# yellowstone-walach-aerospace-cubesat-sch.net
KiCad netlist of a schematic drawn in EAGLE
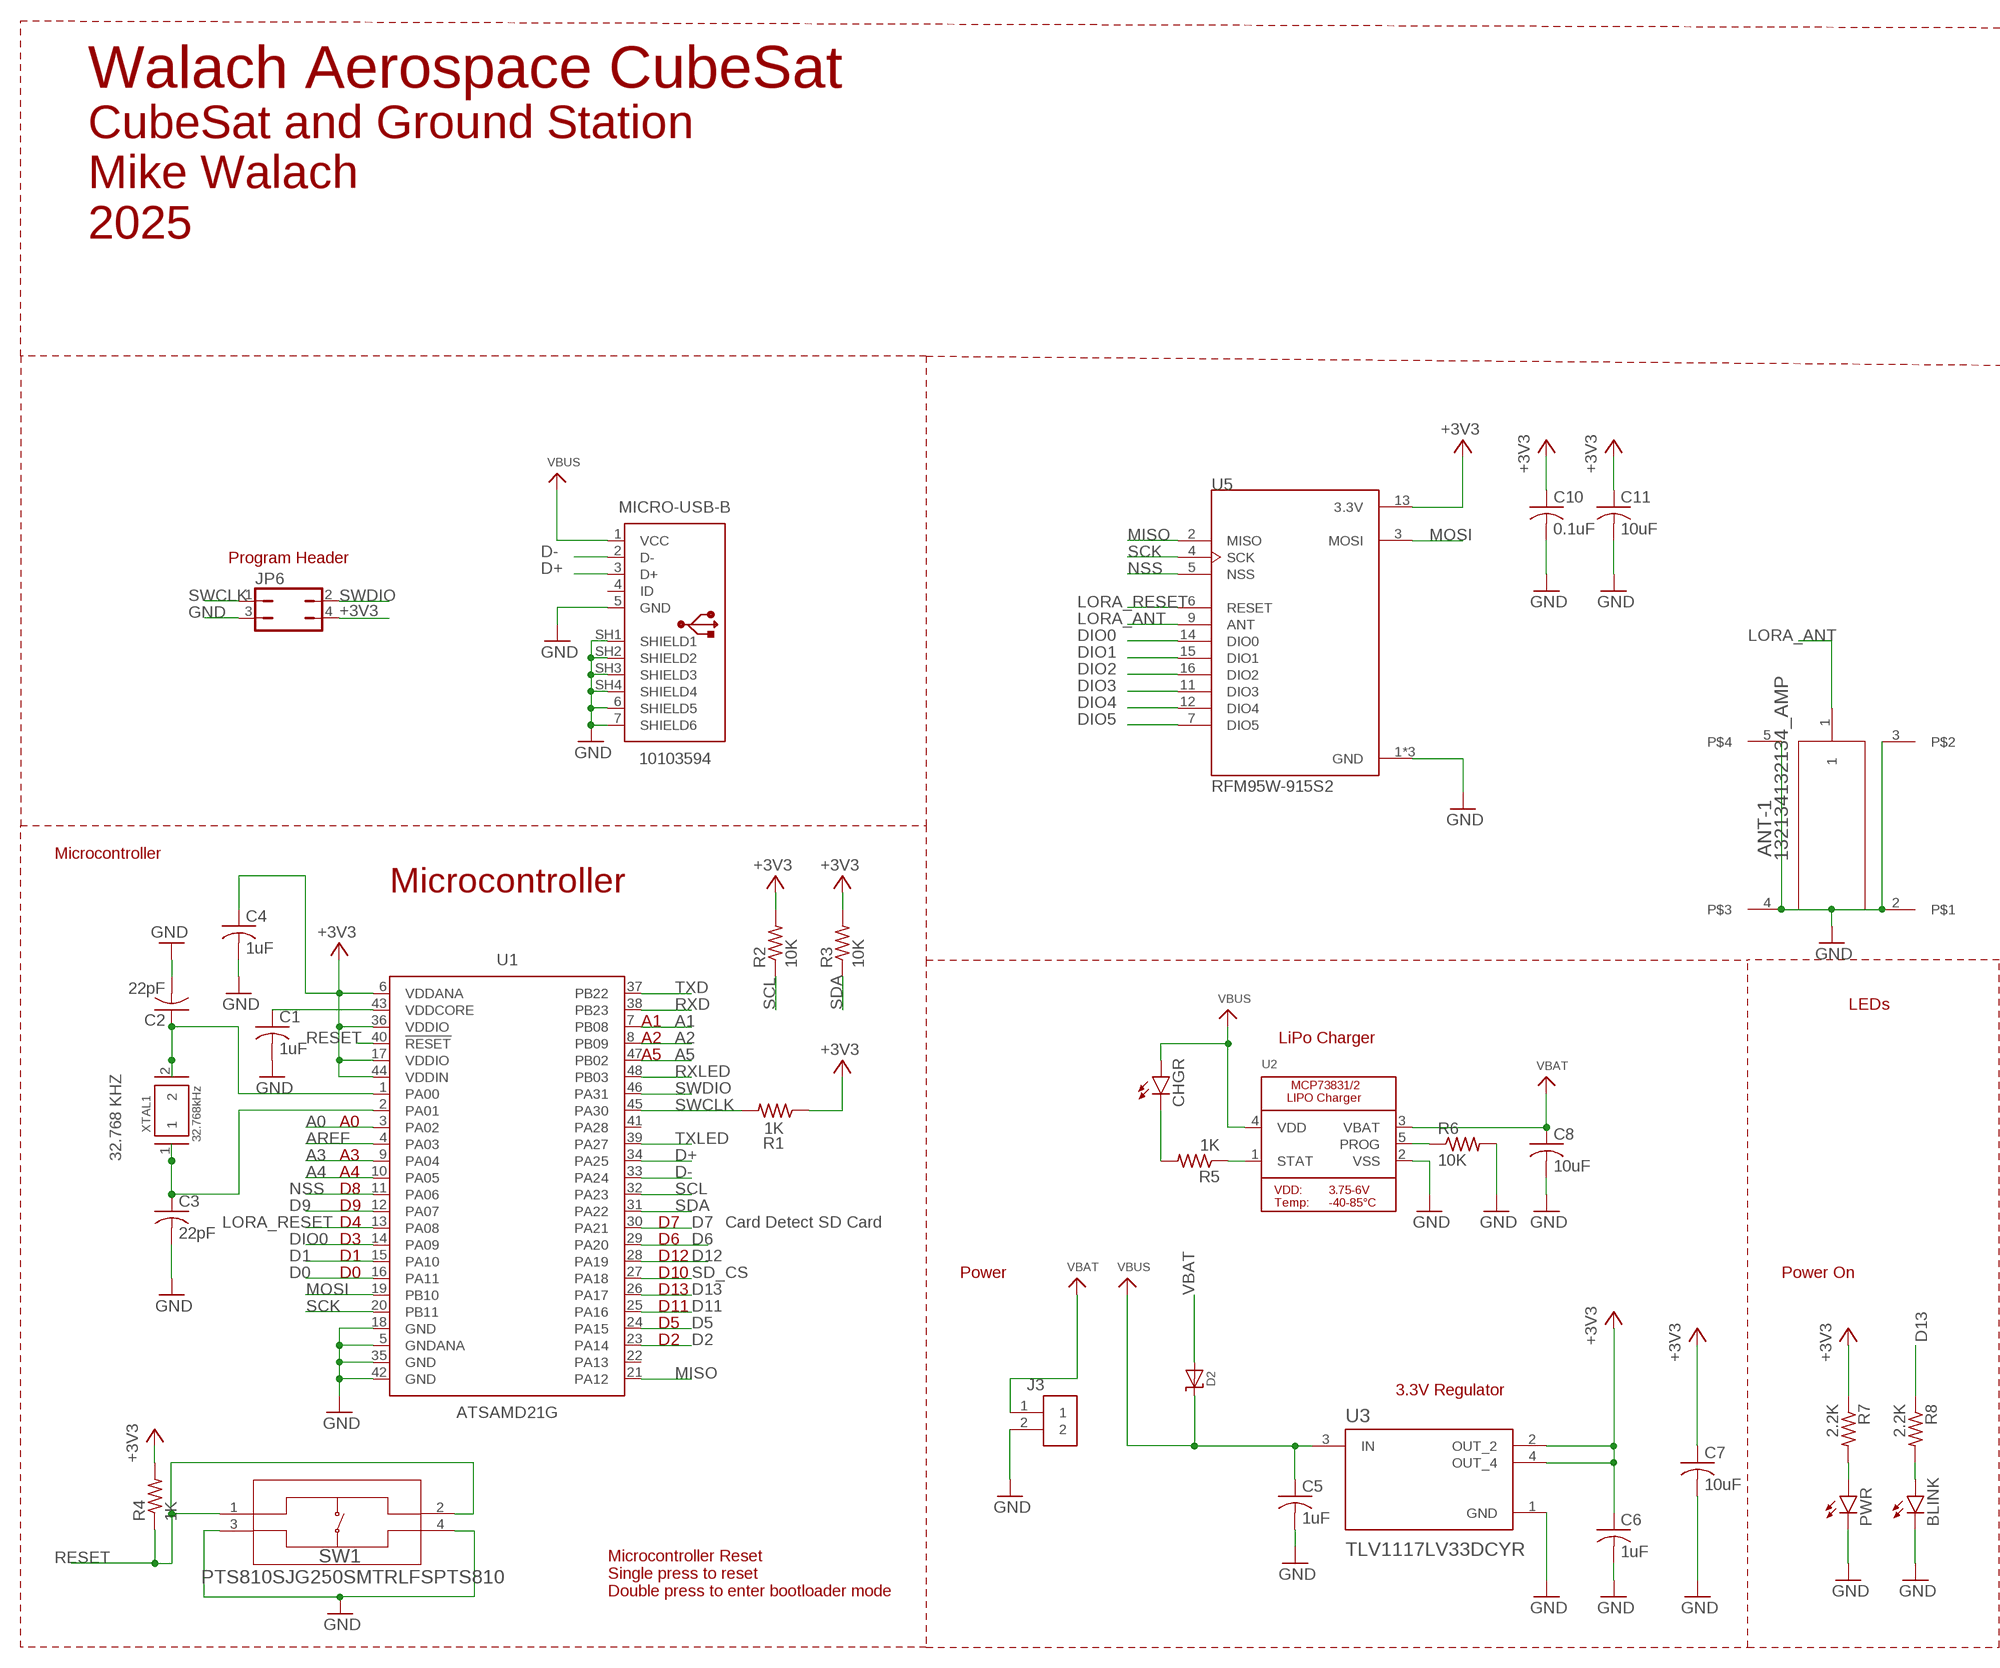
[diagram p0: schematic, sheet 1, part 1 of 2]
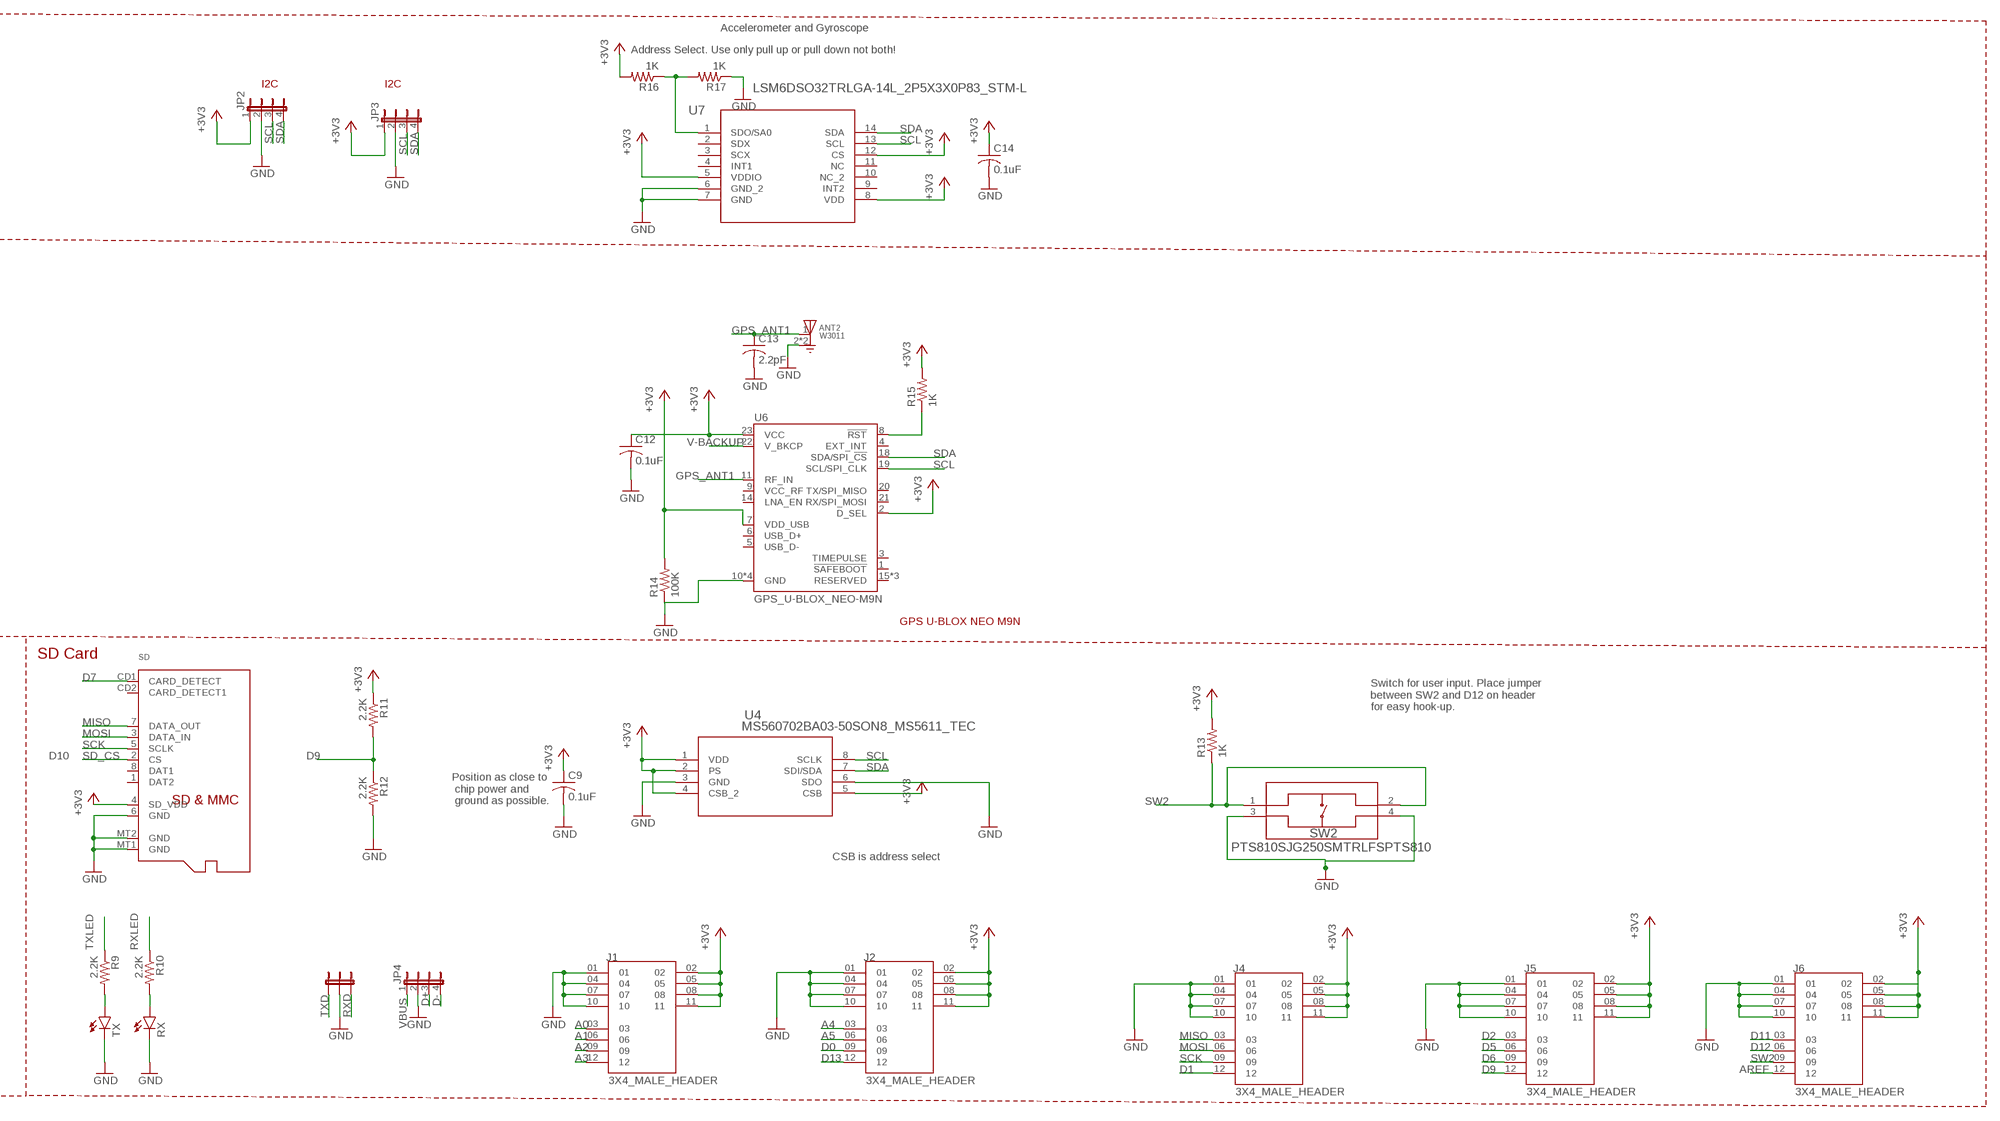
[diagram p1: schematic, sheet 1, part 2 of 2]

(export (version "E")
  (design (tool "Eeschema 10.0.6"))
  (components
    (comp (ref "ANT-1")
      (value "132134132134_AMP")
      (footprint "eagle-import:132134_AMP")
      (fields
        (field (name "MANUFACTURER_PART_NUMBER") "132134")
        (field (name "COPYRIGHT") "Copyright (C) 2025 Ultra Librarian. All rights reserved.")
      )
      (libsource (lib "eagle-import") (part "132134132134_AMP"))
    )
    (comp (ref "ANT2")
      (value "W3011")
      (footprint "eagle-import:XDCR_W3011")
      (fields (field (name "MANUFACTURER") "PulseLarsen"))
      (libsource (lib "eagle-import") (part "W3011"))
    )
    (comp (ref "BLINK")
      (value "LEDSML0805")
      (footprint "eagle-import:SML0805")
      (libsource (lib "eagle-import") (part "LEDSML0805"))
    )
    (comp (ref "C1")
      (value "1uF")
      (footprint "eagle-import:C0805")
      (libsource (lib "eagle-import") (part "C-USC0805"))
    )
    (comp (ref "C2")
      (value "22pF")
      (footprint "eagle-import:C0805")
      (libsource (lib "eagle-import") (part "C-USC0805"))
    )
    (comp (ref "C3")
      (value "22pF")
      (footprint "eagle-import:C0805")
      (libsource (lib "eagle-import") (part "C-USC0805"))
    )
    (comp (ref "C4")
      (value "1uF")
      (footprint "eagle-import:C0805")
      (libsource (lib "eagle-import") (part "C-USC0805"))
    )
    (comp (ref "C5")
      (value "1uF")
      (footprint "eagle-import:C0805")
      (libsource (lib "eagle-import") (part "C-USC0805"))
    )
    (comp (ref "C6")
      (value "1uF")
      (footprint "eagle-import:C0805")
      (libsource (lib "eagle-import") (part "C-USC0805"))
    )
    (comp (ref "C7")
      (value "10uF")
      (footprint "eagle-import:C0805")
      (libsource (lib "eagle-import") (part "C-USC0805"))
    )
    (comp (ref "C8")
      (value "10uF")
      (footprint "eagle-import:C0805")
      (libsource (lib "eagle-import") (part "C-USC0805"))
    )
    (comp (ref "C9")
      (value "0.1uF")
      (footprint "eagle-import:C0805")
      (libsource (lib "eagle-import") (part "C-USC0805"))
    )
    (comp (ref "C10")
      (value "0.1uF")
      (footprint "eagle-import:C0805")
      (libsource (lib "eagle-import") (part "C-USC0805"))
    )
    (comp (ref "C11")
      (value "10uF")
      (footprint "eagle-import:C0805")
      (libsource (lib "eagle-import") (part "C-USC0805"))
    )
    (comp (ref "C12")
      (value "0.1uF")
      (footprint "eagle-import:C0805")
      (libsource (lib "eagle-import") (part "C-USC0805"))
    )
    (comp (ref "C13")
      (value "2.2pF")
      (footprint "eagle-import:C0805")
      (libsource (lib "eagle-import") (part "C-USC0805"))
    )
    (comp (ref "C14")
      (value "0.1uF")
      (footprint "eagle-import:C0805")
      (libsource (lib "eagle-import") (part "C-USC0805"))
    )
    (comp (ref "CHGR")
      (value "LEDSML0805")
      (footprint "eagle-import:SML0805")
      (libsource (lib "eagle-import") (part "LEDSML0805"))
    )
    (comp (ref "D2")
      (value "MICROBUILDER_DIODE-SCHOTTKYSOD-123")
      (footprint "eagle-import:MICROBUILDER_SOD-123")
      (libsource (lib "eagle-import") (part "MICROBUILDER_DIODE-SCHOTTKYSOD-123"))
    )
    (comp (ref "J1")
      (value "3X4_MALE_HEADER")
      (footprint "eagle-import:TSW-104-07-F-T_SAMTEC_TSW-104-07-F-T")
      (fields (field (name "MANUFACTURER") "Samtec"))
      (libsource (lib "eagle-import") (part "3X4_MALE_HEADER"))
    )
    (comp (ref "J2")
      (value "3X4_MALE_HEADER")
      (footprint "eagle-import:TSW-104-07-F-T_SAMTEC_TSW-104-07-F-T")
      (fields (field (name "MANUFACTURER") "Samtec"))
      (libsource (lib "eagle-import") (part "3X4_MALE_HEADER"))
    )
    (comp (ref "J3")
      (value "S2B-PH-K-S(LF)(SN)")
      (footprint "eagle-import:S2B-PH-K-S(LF)(SN)")
      (fields
        (field (name "DIGI_KEY_PART_NUMBER") "455-1719-ND")
        (field (name "MANUFACTURER") "JST Sales America Inc.")
        (field (name "CREATED_BY") "PCBLayout.com")
      )
      (libsource (lib "eagle-import") (part "S2B-PH-K-S(LF)(SN)"))
    )
    (comp (ref "J4")
      (value "3X4_MALE_HEADER")
      (footprint "eagle-import:TSW-104-07-F-T_SAMTEC_TSW-104-07-F-T")
      (fields (field (name "MANUFACTURER") "Samtec"))
      (libsource (lib "eagle-import") (part "3X4_MALE_HEADER"))
    )
    (comp (ref "J5")
      (value "3X4_MALE_HEADER")
      (footprint "eagle-import:TSW-104-07-F-T_SAMTEC_TSW-104-07-F-T")
      (fields (field (name "MANUFACTURER") "Samtec"))
      (libsource (lib "eagle-import") (part "3X4_MALE_HEADER"))
    )
    (comp (ref "J6")
      (value "3X4_MALE_HEADER")
      (footprint "eagle-import:TSW-104-07-F-T_SAMTEC_TSW-104-07-F-T")
      (fields (field (name "MANUFACTURER") "Samtec"))
      (libsource (lib "eagle-import") (part "3X4_MALE_HEADER"))
    )
    (comp (ref "JP2")
      (value "JP4E")
      (footprint "eagle-import:JP4")
      (libsource (lib "eagle-import") (part "JP4E"))
    )
    (comp (ref "JP3")
      (value "JP4E")
      (footprint "eagle-import:JP4")
      (libsource (lib "eagle-import") (part "JP4E"))
    )
    (comp (ref "JP4")
      (value "JP4E")
      (footprint "eagle-import:JP4")
      (libsource (lib "eagle-import") (part "JP4E"))
    )
    (comp (ref "JP5")
      (value "3-PIN-JUMPER")
      (footprint "eagle-import:3-PIN-JUMPER")
      (libsource (lib "eagle-import") (part "3-PIN-JUMPER"))
    )
    (comp (ref "JP6")
      (value "JP2Q")
      (footprint "eagle-import:JP2Q")
      (libsource (lib "eagle-import") (part "JP2Q"))
    )
    (comp (ref "MICRO-USB-B")
      (value "10103594")
      (footprint "eagle-import:10103594")
      (fields (field (name "MANUFACTURER") "Amphenol ICC (FCI)") (field (name "MPN") "10103594-0001LF"))
      (libsource (lib "eagle-import") (part "10103594"))
    )
    (comp (ref "PWR")
      (value "LEDSML0805")
      (footprint "eagle-import:SML0805")
      (libsource (lib "eagle-import") (part "LEDSML0805"))
    )
    (comp (ref "R1")
      (value "1K")
      (footprint "eagle-import:R0805")
      (libsource (lib "eagle-import") (part "R-US_R0805"))
    )
    (comp (ref "R2")
      (value "10K")
      (footprint "eagle-import:R0805")
      (libsource (lib "eagle-import") (part "R-US_R0805"))
    )
    (comp (ref "R3")
      (value "10K")
      (footprint "eagle-import:R0805")
      (libsource (lib "eagle-import") (part "R-US_R0805"))
    )
    (comp (ref "R4")
      (value "1K")
      (footprint "eagle-import:R0805")
      (libsource (lib "eagle-import") (part "R-US_R0805"))
    )
    (comp (ref "R5")
      (value "1K")
      (footprint "eagle-import:R0805")
      (libsource (lib "eagle-import") (part "R-US_R0805"))
    )
    (comp (ref "R6")
      (value "10K")
      (footprint "eagle-import:R0805")
      (libsource (lib "eagle-import") (part "R-US_R0805"))
    )
    (comp (ref "R7")
      (value "2.2K")
      (footprint "eagle-import:R0805")
      (libsource (lib "eagle-import") (part "R-US_R0805"))
    )
    (comp (ref "R8")
      (value "2.2K")
      (footprint "eagle-import:R0805")
      (libsource (lib "eagle-import") (part "R-US_R0805"))
    )
    (comp (ref "R9")
      (value "2.2K")
      (footprint "eagle-import:R0805")
      (libsource (lib "eagle-import") (part "R-US_R0805"))
    )
    (comp (ref "R10")
      (value "2.2K")
      (footprint "eagle-import:R0805")
      (libsource (lib "eagle-import") (part "R-US_R0805"))
    )
    (comp (ref "R11")
      (value "2.2K")
      (footprint "eagle-import:R0805")
      (libsource (lib "eagle-import") (part "R-US_R0805"))
    )
    (comp (ref "R12")
      (value "2.2K")
      (footprint "eagle-import:R0805")
      (libsource (lib "eagle-import") (part "R-US_R0805"))
    )
    (comp (ref "R13")
      (value "1K")
      (footprint "eagle-import:R0805")
      (libsource (lib "eagle-import") (part "R-US_R0805"))
    )
    (comp (ref "R14")
      (value "100K")
      (footprint "eagle-import:R0805")
      (libsource (lib "eagle-import") (part "R-US_R0805"))
    )
    (comp (ref "R15")
      (value "1K")
      (footprint "eagle-import:R0805")
      (libsource (lib "eagle-import") (part "R-US_R0805"))
    )
    (comp (ref "R16")
      (value "1K")
      (footprint "eagle-import:R0805")
      (libsource (lib "eagle-import") (part "R-US_R0805"))
    )
    (comp (ref "R17")
      (value "1K")
      (footprint "eagle-import:R0805")
      (libsource (lib "eagle-import") (part "R-US_R0805"))
    )
    (comp (ref "RX")
      (value "LEDSML0805")
      (footprint "eagle-import:SML0805")
      (libsource (lib "eagle-import") (part "LEDSML0805"))
    )
    (comp (ref "SD")
      (value "MICROBUILDER_MICROSD")
      (footprint "eagle-import:MICROBUILDER_MICROSD")
      (libsource (lib "eagle-import") (part "MICROBUILDER_MICROSD"))
    )
    (comp (ref "SW1")
      (value "PTS810SJG250SMTRLFSPTS810")
      (footprint "eagle-import:PTS810")
      (fields
        (field (name "MANUFACTURER_PART_NUMBER") "PTS810SJG250SMTRLFS")
        (field (name "COPYRIGHT") "Copyright (C) 2024 Ultra Librarian. All rights reserved.")
      )
      (libsource (lib "eagle-import") (part "PTS810SJG250SMTRLFSPTS810"))
    )
    (comp (ref "SW2")
      (value "PTS810SJG250SMTRLFSPTS810")
      (footprint "eagle-import:PTS810")
      (fields
        (field (name "MANUFACTURER_PART_NUMBER") "PTS810SJG250SMTRLFS")
        (field (name "COPYRIGHT") "Copyright (C) 2024 Ultra Librarian. All rights reserved.")
      )
      (libsource (lib "eagle-import") (part "PTS810SJG250SMTRLFSPTS810"))
    )
    (comp (ref "TX")
      (value "LEDSML0805")
      (footprint "eagle-import:SML0805")
      (libsource (lib "eagle-import") (part "LEDSML0805"))
    )
    (comp (ref "U1")
      (value "ATSAMD21G")
      (footprint "eagle-import:QFP50P900X900X120-48")
      (fields (field (name "MANUFACTURER") "Microchip Technology"))
      (libsource (lib "eagle-import") (part "ATSAMD21G_TQFP"))
    )
    (comp (ref "U2")
      (value "MICROBUILDER_MCP73831/2")
      (footprint "eagle-import:MICROBUILDER_SOT23-5")
      (libsource (lib "eagle-import") (part "MICROBUILDER_MCP73831/2"))
    )
    (comp (ref "U3")
      (value "TLV1117LV33DCYR")
      (footprint "eagle-import:VREG_TLV1117LV33DCYR")
      (fields (field (name "MANUFACTURER") "Texas Instruments"))
      (libsource (lib "eagle-import") (part "TLV1117LV33DCYR"))
    )
    (comp (ref "U4")
      (value "MS560702BA03-50SON8_MS5611_TEC")
      (footprint "eagle-import:SON8_MS5611_TEC")
      (fields
        (field (name "MANUFACTURER_PART_NUMBER") "MS560702BA03-50")
        (field (name "COPYRIGHT") "Copyright (C) 2025 Ultra Librarian. All rights reserved.")
      )
      (libsource (lib "eagle-import") (part "MS560702BA03-50SON8_MS5611_TEC"))
    )
    (comp (ref "U5")
      (value "RFM95W-915S2")
      (footprint "eagle-import:XCVR_RFM95W-915S2")
      (fields (field (name "MF") "RF Solutions"))
      (libsource (lib "eagle-import") (part "RFM95W-915S2"))
    )
    (comp (ref "U6")
      (value "GPS_U-BLOX_NEO-M9N")
      (footprint "eagle-import:GPS_NEO-M9N")
      (libsource (lib "eagle-import") (part "GPS_U-BLOX_NEO-M9N"))
    )
    (comp (ref "U7")
      (value "LSM6DSO32TRLGA-14L_2P5X3X0P83_STM-L")
      (footprint "eagle-import:LGA-14L_2P5X3X0P83_STM-L")
      (fields
        (field (name "MANUFACTURER_PART_NUMBER") "LSM6DSO32TR")
        (field (name "COPYRIGHT") "Copyright (C) 2023 Ultra Librarian. All rights reserved.")
      )
      (libsource (lib "eagle-import") (part "LSM6DSO32TRLGA-14L_2P5X3X0P83_STM-L"))
    )
    (comp (ref "XTAL1")
      (value "32.768kHz")
      (footprint "eagle-import:XTAL_ABS07-32.768KHZ-T")
      (fields (field (name "MANUFACTURER") "Abracon LLC") (field (name "MPN") "ABS07-32.768KHZ-T "))
      (libsource (lib "eagle-import") (part "ABSO7"))
    )
  )
  (nets
    (net (code "1") (name "+3V3") (class "Default")
      (node (ref "C10") (pin "1") (pinfunction "1_1") (pintype "passive"))
      (node (ref "C11") (pin "1") (pinfunction "1_1") (pintype "passive"))
      (node (ref "C12") (pin "1") (pinfunction "1_1") (pintype "passive"))
      (node (ref "C14") (pin "1") (pinfunction "1_1") (pintype "passive"))
      (node (ref "C4") (pin "1") (pinfunction "1_1") (pintype "passive"))
      (node (ref "C6") (pin "1") (pinfunction "1_1") (pintype "passive"))
      (node (ref "C7") (pin "1") (pinfunction "1_1") (pintype "passive"))
      (node (ref "C9") (pin "1") (pinfunction "1_1") (pintype "passive"))
      (node (ref "J1") (pin "02") (pinfunction "02_02") (pintype "passive"))
      (node (ref "J1") (pin "05") (pinfunction "05_05") (pintype "passive"))
      (node (ref "J1") (pin "08") (pinfunction "08_08") (pintype "passive"))
      (node (ref "J1") (pin "11") (pinfunction "11_11") (pintype "passive"))
      (node (ref "J2") (pin "02") (pinfunction "02_02") (pintype "passive"))
      (node (ref "J2") (pin "05") (pinfunction "05_05") (pintype "passive"))
      (node (ref "J2") (pin "08") (pinfunction "08_08") (pintype "passive"))
      (node (ref "J2") (pin "11") (pinfunction "11_11") (pintype "passive"))
      (node (ref "J4") (pin "02") (pinfunction "02_02") (pintype "passive"))
      (node (ref "J4") (pin "05") (pinfunction "05_05") (pintype "passive"))
      (node (ref "J4") (pin "08") (pinfunction "08_08") (pintype "passive"))
      (node (ref "J4") (pin "11") (pinfunction "11_11") (pintype "passive"))
      (node (ref "J5") (pin "02") (pinfunction "02_02") (pintype "passive"))
      (node (ref "J5") (pin "05") (pinfunction "05_05") (pintype "passive"))
      (node (ref "J5") (pin "08") (pinfunction "08_08") (pintype "passive"))
      (node (ref "J5") (pin "11") (pinfunction "11_11") (pintype "passive"))
      (node (ref "J6") (pin "02") (pinfunction "02_02") (pintype "passive"))
      (node (ref "J6") (pin "05") (pinfunction "05_05") (pintype "passive"))
      (node (ref "J6") (pin "08") (pinfunction "08_08") (pintype "passive"))
      (node (ref "J6") (pin "11") (pinfunction "11_11") (pintype "passive"))
      (node (ref "JP2") (pin "1") (pinfunction "1_1") (pintype "passive"))
      (node (ref "JP3") (pin "1") (pinfunction "1_1") (pintype "passive"))
      (node (ref "JP6") (pin "4") (pinfunction "4_4") (pintype "passive"))
      (node (ref "R1") (pin "1") (pinfunction "1_1") (pintype "passive"))
      (node (ref "R11") (pin "1") (pinfunction "1_1") (pintype "passive"))
      (node (ref "R13") (pin "2") (pinfunction "2_2") (pintype "passive"))
      (node (ref "R14") (pin "2") (pinfunction "2_2") (pintype "passive"))
      (node (ref "R15") (pin "2") (pinfunction "2_2") (pintype "passive"))
      (node (ref "R16") (pin "2") (pinfunction "2_2") (pintype "passive"))
      (node (ref "R2") (pin "2") (pinfunction "2_2") (pintype "passive"))
      (node (ref "R3") (pin "2") (pinfunction "2_2") (pintype "passive"))
      (node (ref "R4") (pin "2") (pinfunction "2_2") (pintype "passive"))
      (node (ref "R7") (pin "1") (pinfunction "1_1") (pintype "passive"))
      (node (ref "SD") (pin "4") (pinfunction "SD_VDD_4") (pintype "power_in"))
      (node (ref "U1") (pin "17") (pinfunction "VDDIO_17") (pintype "power_in"))
      (node (ref "U1") (pin "36") (pinfunction "VDDIO_36") (pintype "power_in"))
      (node (ref "U1") (pin "44") (pinfunction "VDDIN_44") (pintype "power_in"))
      (node (ref "U1") (pin "6") (pinfunction "VDDANA_6") (pintype "power_in"))
      (node (ref "U3") (pin "2") (pinfunction "OUT_2_2") (pintype "output"))
      (node (ref "U3") (pin "4") (pinfunction "OUT_4_4") (pintype "output"))
      (node (ref "U4") (pin "1") (pinfunction "VDD_1") (pintype "power_in"))
      (node (ref "U4") (pin "2") (pinfunction "PS_2") (pintype "input"))
      (node (ref "U4") (pin "4") (pinfunction "CSB_2_4") (pintype "input"))
      (node (ref "U4") (pin "5") (pinfunction "CSB_5") (pintype "input"))
      (node (ref "U5") (pin "13") (pinfunction "3.3V_13") (pintype "power_in"))
      (node (ref "U6") (pin "2") (pinfunction "D_SEL_2") (pintype "bidirectional"))
      (node (ref "U6") (pin "23") (pinfunction "VCC_23") (pintype "bidirectional"))
      (node (ref "U6") (pin "7") (pinfunction "VDD_USB_7") (pintype "bidirectional"))
      (node (ref "U7") (pin "12") (pinfunction "CS_12") (pintype "input"))
      (node (ref "U7") (pin "5") (pinfunction "VDDIO_5") (pintype "power_in"))
      (node (ref "U7") (pin "8") (pinfunction "VDD_8") (pintype "power_in"))
    )
    (net (code "2") (name "/A0") (class "Default")
      (node (ref "J1") (pin "03") (pinfunction "03_03") (pintype "passive"))
      (node (ref "U1") (pin "3") (pinfunction "PA02_3") (pintype "bidirectional"))
    )
    (net (code "3") (name "/A1") (class "Default")
      (node (ref "J1") (pin "06") (pinfunction "06_06") (pintype "passive"))
      (node (ref "U1") (pin "7") (pinfunction "PB08_7") (pintype "bidirectional"))
    )
    (net (code "4") (name "/A2") (class "Default")
      (node (ref "J1") (pin "09") (pinfunction "09_09") (pintype "passive"))
      (node (ref "U1") (pin "8") (pinfunction "PB09_8") (pintype "bidirectional"))
    )
    (net (code "5") (name "/A3") (class "Default")
      (node (ref "J1") (pin "12") (pinfunction "12_12") (pintype "passive"))
      (node (ref "U1") (pin "9") (pinfunction "PA04_9") (pintype "bidirectional"))
    )
    (net (code "6") (name "/A4") (class "Default")
      (node (ref "J2") (pin "03") (pinfunction "03_03") (pintype "passive"))
      (node (ref "U1") (pin "10") (pinfunction "PA05_10") (pintype "bidirectional"))
    )
    (net (code "7") (name "/A5") (class "Default")
      (node (ref "J2") (pin "06") (pinfunction "06_06") (pintype "passive"))
      (node (ref "U1") (pin "47") (pinfunction "PB02_47") (pintype "bidirectional"))
    )
    (net (code "8") (name "/AREF") (class "Default")
      (node (ref "J6") (pin "12") (pinfunction "12_12") (pintype "passive"))
      (node (ref "U1") (pin "4") (pinfunction "PA03_4") (pintype "bidirectional"))
    )
    (net (code "9") (name "/D+") (class "Default")
      (node (ref "JP4") (pin "3") (pinfunction "3_3") (pintype "passive"))
      (node (ref "MICRO-USB-B") (pin "3") (pinfunction "D+_3") (pintype "bidirectional"))
      (node (ref "U1") (pin "34") (pinfunction "PA25_34") (pintype "bidirectional"))
    )
    (net (code "10") (name "/D-") (class "Default")
      (node (ref "JP4") (pin "4") (pinfunction "4_4") (pintype "passive"))
      (node (ref "MICRO-USB-B") (pin "2") (pinfunction "D-_2") (pintype "bidirectional"))
      (node (ref "U1") (pin "33") (pinfunction "PA24_33") (pintype "bidirectional"))
    )
    (net (code "11") (name "/D0") (class "Default")
      (node (ref "J2") (pin "09") (pinfunction "09_09") (pintype "passive"))
      (node (ref "U1") (pin "16") (pinfunction "PA11_16") (pintype "bidirectional"))
    )
    (net (code "12") (name "/D1") (class "Default")
      (node (ref "J4") (pin "12") (pinfunction "12_12") (pintype "passive"))
      (node (ref "U1") (pin "15") (pinfunction "PA10_15") (pintype "bidirectional"))
    )
    (net (code "13") (name "/D2") (class "Default")
      (node (ref "J5") (pin "03") (pinfunction "03_03") (pintype "passive"))
      (node (ref "U1") (pin "23") (pinfunction "PA14_23") (pintype "output"))
    )
    (net (code "14") (name "/D5") (class "Default")
      (node (ref "J5") (pin "06") (pinfunction "06_06") (pintype "passive"))
      (node (ref "U1") (pin "24") (pinfunction "PA15_24") (pintype "output"))
    )
    (net (code "15") (name "/D6") (class "Default")
      (node (ref "J5") (pin "09") (pinfunction "09_09") (pintype "passive"))
      (node (ref "U1") (pin "29") (pinfunction "PA20_29") (pintype "bidirectional"))
    )
    (net (code "16") (name "/D7") (class "Default")
      (node (ref "SD") (pin "CD1") (pinfunction "CARD_DETECT_CD1") (pintype "passive"))
      (node (ref "U1") (pin "30") (pinfunction "PA21_30") (pintype "bidirectional"))
    )
    (net (code "17") (name "/D9") (class "Default")
      (node (ref "J5") (pin "12") (pinfunction "12_12") (pintype "passive"))
      (node (ref "R11") (pin "2") (pinfunction "2_2") (pintype "passive"))
      (node (ref "R12") (pin "1") (pinfunction "1_1") (pintype "passive"))
      (node (ref "U1") (pin "12") (pinfunction "PA07_12") (pintype "bidirectional"))
    )
    (net (code "18") (name "/D11") (class "Default")
      (node (ref "J6") (pin "03") (pinfunction "03_03") (pintype "passive"))
      (node (ref "U1") (pin "25") (pinfunction "PA16_25") (pintype "bidirectional"))
    )
    (net (code "19") (name "/D12") (class "Default")
      (node (ref "J6") (pin "06") (pinfunction "06_06") (pintype "passive"))
      (node (ref "U1") (pin "28") (pinfunction "PA19_28") (pintype "bidirectional"))
    )
    (net (code "20") (name "/D13") (class "Default")
      (node (ref "J2") (pin "12") (pinfunction "12_12") (pintype "passive"))
      (node (ref "R8") (pin "1") (pinfunction "1_1") (pintype "passive"))
      (node (ref "U1") (pin "26") (pinfunction "PA17_26") (pintype "bidirectional"))
    )
    (net (code "21") (name "/DIO0") (class "Default")
      (node (ref "U1") (pin "14") (pinfunction "PA09_14") (pintype "bidirectional"))
      (node (ref "U5") (pin "14") (pinfunction "DIO0_14") (pintype "bidirectional"))
    )
    (net (code "22") (name "/DIO1") (class "Default")
      (node (ref "U5") (pin "15") (pinfunction "DIO1_15") (pintype "bidirectional"))
    )
    (net (code "23") (name "/DIO2") (class "Default")
      (node (ref "U5") (pin "16") (pinfunction "DIO2_16") (pintype "bidirectional"))
    )
    (net (code "24") (name "/DIO3") (class "Default")
      (node (ref "U5") (pin "11") (pinfunction "DIO3_11") (pintype "bidirectional"))
    )
    (net (code "25") (name "/DIO4") (class "Default")
      (node (ref "U5") (pin "12") (pinfunction "DIO4_12") (pintype "bidirectional"))
    )
    (net (code "26") (name "/DIO5") (class "Default")
      (node (ref "U5") (pin "7") (pinfunction "DIO5_7") (pintype "bidirectional"))
    )
    (net (code "27") (name "/GPS_ANT1") (class "Default")
      (node (ref "ANT2") (pin "1") (pinfunction "FEED_1") (pintype "passive"))
      (node (ref "C13") (pin "1") (pinfunction "1_1") (pintype "passive"))
      (node (ref "U6") (pin "11") (pinfunction "RF_IN_11") (pintype "bidirectional"))
    )
    (net (code "28") (name "/LORA_ANT") (class "Default")
      (node (ref "ANT-1") (pin "1") (pinfunction "1_1") (pintype "passive"))
      (node (ref "U5") (pin "9") (pinfunction "ANT_9") (pintype "bidirectional"))
    )
    (net (code "29") (name "/LORA_RESET") (class "Default")
      (node (ref "U1") (pin "13") (pinfunction "PA08_13") (pintype "bidirectional"))
      (node (ref "U5") (pin "6") (pinfunction "RESET_6") (pintype "bidirectional"))
    )
    (net (code "30") (name "/MISO") (class "Default")
      (node (ref "J4") (pin "03") (pinfunction "03_03") (pintype "passive"))
      (node (ref "SD") (pin "7") (pinfunction "DATA_OUT_7") (pintype "output"))
      (node (ref "U1") (pin "21") (pinfunction "PA12_21") (pintype "bidirectional"))
      (node (ref "U5") (pin "2") (pinfunction "MISO_2") (pintype "input"))
    )
    (net (code "31") (name "/MOSI") (class "Default")
      (node (ref "J4") (pin "06") (pinfunction "06_06") (pintype "passive"))
      (node (ref "SD") (pin "3") (pinfunction "DATA_IN_3") (pintype "input"))
      (node (ref "U1") (pin "19") (pinfunction "PB10_19") (pintype "bidirectional"))
      (node (ref "U5") (pin "3") (pinfunction "MOSI_3") (pintype "output"))
    )
    (net (code "32") (name "/NSS") (class "Default")
      (node (ref "U1") (pin "11") (pinfunction "PA06_11") (pintype "bidirectional"))
      (node (ref "U5") (pin "5") (pinfunction "NSS_5") (pintype "input"))
    )
    (net (code "33") (name "/RESET") (class "Default")
      (node (ref "R4") (pin "1") (pinfunction "1_1") (pintype "passive"))
      (node (ref "SW1") (pin "1") (pinfunction "1_1") (pintype "passive"))
      (node (ref "SW1") (pin "2") (pinfunction "2_2") (pintype "passive"))
      (node (ref "U1") (pin "40") (pinfunction "~{RESET}_40") (pintype "input"))
    )
    (net (code "34") (name "/RXD") (class "Default")
      (node (ref "JP5") (pin "3") (pinfunction "P$3_3") (pintype "bidirectional"))
      (node (ref "U1") (pin "38") (pinfunction "PB23_38") (pintype "bidirectional"))
    )
    (net (code "35") (name "/RXLED") (class "Default")
      (node (ref "R10") (pin "1") (pinfunction "1_1") (pintype "passive"))
      (node (ref "U1") (pin "48") (pinfunction "PB03_48") (pintype "bidirectional"))
    )
    (net (code "36") (name "/SCK") (class "Default")
      (node (ref "J4") (pin "09") (pinfunction "09_09") (pintype "passive"))
      (node (ref "SD") (pin "5") (pinfunction "SCLK_5") (pintype "input"))
      (node (ref "U1") (pin "20") (pinfunction "PB11_20") (pintype "bidirectional"))
      (node (ref "U5") (pin "4") (pinfunction "SCK_4") (pintype "input"))
    )
    (net (code "37") (name "/SCL") (class "Default")
      (node (ref "JP2") (pin "3") (pinfunction "3_3") (pintype "passive"))
      (node (ref "JP3") (pin "3") (pinfunction "3_3") (pintype "passive"))
      (node (ref "R2") (pin "1") (pinfunction "1_1") (pintype "passive"))
      (node (ref "U1") (pin "32") (pinfunction "PA23_32") (pintype "bidirectional"))
      (node (ref "U4") (pin "8") (pinfunction "SCLK_8") (pintype "input"))
      (node (ref "U6") (pin "19") (pinfunction "SCL/SPI_CLK_19") (pintype "bidirectional"))
      (node (ref "U7") (pin "13") (pinfunction "SCL_13") (pintype "input"))
    )
    (net (code "38") (name "/SDA") (class "Default")
      (node (ref "JP2") (pin "4") (pinfunction "4_4") (pintype "passive"))
      (node (ref "JP3") (pin "4") (pinfunction "4_4") (pintype "passive"))
      (node (ref "R3") (pin "1") (pinfunction "1_1") (pintype "passive"))
      (node (ref "U1") (pin "31") (pinfunction "PA22_31") (pintype "bidirectional"))
      (node (ref "U4") (pin "7") (pinfunction "SDI/SDA_7") (pintype "bidirectional"))
      (node (ref "U6") (pin "18") (pinfunction "SDA/SPI_~{CS}_18") (pintype "bidirectional"))
      (node (ref "U7") (pin "14") (pinfunction "SDA_14") (pintype "bidirectional"))
    )
    (net (code "39") (name "/SD_CS") (class "Default")
      (node (ref "SD") (pin "2") (pinfunction "CS_2") (pintype "input"))
      (node (ref "U1") (pin "27") (pinfunction "PA18_27") (pintype "bidirectional"))
    )
    (net (code "40") (name "/SW2") (class "Default")
      (node (ref "J6") (pin "09") (pinfunction "09_09") (pintype "passive"))
      (node (ref "R13") (pin "1") (pinfunction "1_1") (pintype "passive"))
      (node (ref "SW2") (pin "1") (pinfunction "1_1") (pintype "passive"))
      (node (ref "SW2") (pin "2") (pinfunction "2_2") (pintype "passive"))
    )
    (net (code "41") (name "/SWCLK") (class "Default")
      (node (ref "JP6") (pin "1") (pinfunction "1_1") (pintype "passive"))
      (node (ref "R1") (pin "2") (pinfunction "2_2") (pintype "passive"))
      (node (ref "U1") (pin "45") (pinfunction "PA30_45") (pintype "bidirectional"))
    )
    (net (code "42") (name "/SWDIO") (class "Default")
      (node (ref "JP6") (pin "2") (pinfunction "2_2") (pintype "passive"))
      (node (ref "U1") (pin "46") (pinfunction "PA31_46") (pintype "bidirectional"))
    )
    (net (code "43") (name "/TXD") (class "Default")
      (node (ref "JP5") (pin "1") (pinfunction "P$1_1") (pintype "bidirectional"))
      (node (ref "U1") (pin "37") (pinfunction "PB22_37") (pintype "bidirectional"))
    )
    (net (code "44") (name "/TXLED") (class "Default")
      (node (ref "R9") (pin "1") (pinfunction "1_1") (pintype "passive"))
      (node (ref "U1") (pin "39") (pinfunction "PA27_39") (pintype "bidirectional"))
    )
    (net (code "45") (name "/V-BACKUP") (class "Default")
      (node (ref "U6") (pin "22") (pinfunction "V_BKCP_22") (pintype "bidirectional"))
    )
    (net (code "46") (name "GND") (class "Default")
      (node (ref "ANT-1") (pin "2") (pinfunction "P$1_2") (pintype "bidirectional"))
      (node (ref "ANT-1") (pin "3") (pinfunction "P$2_3") (pintype "bidirectional"))
      (node (ref "ANT-1") (pin "4") (pinfunction "P$3_4") (pintype "bidirectional"))
      (node (ref "ANT-1") (pin "5") (pinfunction "P$4_5") (pintype "bidirectional"))
      (node (ref "ANT2") (pin "2") (pinfunction "GND_2") (pintype "power_in"))
      (node (ref "ANT2") (pin "3") (pinfunction "GND_3") (pintype "power_in"))
      (node (ref "BLINK") (pin "C") (pinfunction "C_C") (pintype "passive"))
      (node (ref "C1") (pin "2") (pinfunction "2_2") (pintype "passive"))
      (node (ref "C10") (pin "2") (pinfunction "2_2") (pintype "passive"))
      (node (ref "C11") (pin "2") (pinfunction "2_2") (pintype "passive"))
      (node (ref "C12") (pin "2") (pinfunction "2_2") (pintype "passive"))
      (node (ref "C13") (pin "2") (pinfunction "2_2") (pintype "passive"))
      (node (ref "C14") (pin "2") (pinfunction "2_2") (pintype "passive"))
      (node (ref "C2") (pin "2") (pinfunction "2_2") (pintype "passive"))
      (node (ref "C3") (pin "2") (pinfunction "2_2") (pintype "passive"))
      (node (ref "C4") (pin "2") (pinfunction "2_2") (pintype "passive"))
      (node (ref "C5") (pin "2") (pinfunction "2_2") (pintype "passive"))
      (node (ref "C6") (pin "2") (pinfunction "2_2") (pintype "passive"))
      (node (ref "C7") (pin "2") (pinfunction "2_2") (pintype "passive"))
      (node (ref "C8") (pin "2") (pinfunction "2_2") (pintype "passive"))
      (node (ref "C9") (pin "2") (pinfunction "2_2") (pintype "passive"))
      (node (ref "J1") (pin "01") (pinfunction "01_01") (pintype "passive"))
      (node (ref "J1") (pin "04") (pinfunction "04_04") (pintype "passive"))
      (node (ref "J1") (pin "07") (pinfunction "07_07") (pintype "passive"))
      (node (ref "J1") (pin "10") (pinfunction "10_10") (pintype "passive"))
      (node (ref "J2") (pin "01") (pinfunction "01_01") (pintype "passive"))
      (node (ref "J2") (pin "04") (pinfunction "04_04") (pintype "passive"))
      (node (ref "J2") (pin "07") (pinfunction "07_07") (pintype "passive"))
      (node (ref "J2") (pin "10") (pinfunction "10_10") (pintype "passive"))
      (node (ref "J3") (pin "2") (pinfunction "2_2") (pintype "passive"))
      (node (ref "J4") (pin "01") (pinfunction "01_01") (pintype "passive"))
      (node (ref "J4") (pin "04") (pinfunction "04_04") (pintype "passive"))
      (node (ref "J4") (pin "07") (pinfunction "07_07") (pintype "passive"))
      (node (ref "J4") (pin "10") (pinfunction "10_10") (pintype "passive"))
      (node (ref "J5") (pin "01") (pinfunction "01_01") (pintype "passive"))
      (node (ref "J5") (pin "04") (pinfunction "04_04") (pintype "passive"))
      (node (ref "J5") (pin "07") (pinfunction "07_07") (pintype "passive"))
      (node (ref "J5") (pin "10") (pinfunction "10_10") (pintype "passive"))
      (node (ref "J6") (pin "01") (pinfunction "01_01") (pintype "passive"))
      (node (ref "J6") (pin "04") (pinfunction "04_04") (pintype "passive"))
      (node (ref "J6") (pin "07") (pinfunction "07_07") (pintype "passive"))
      (node (ref "J6") (pin "10") (pinfunction "10_10") (pintype "passive"))
      (node (ref "JP2") (pin "2") (pinfunction "2_2") (pintype "passive"))
      (node (ref "JP3") (pin "2") (pinfunction "2_2") (pintype "passive"))
      (node (ref "JP4") (pin "2") (pinfunction "2_2") (pintype "passive"))
      (node (ref "JP5") (pin "2") (pinfunction "P$2_2") (pintype "bidirectional"))
      (node (ref "JP6") (pin "3") (pinfunction "3_3") (pintype "passive"))
      (node (ref "MICRO-USB-B") (pin "5") (pinfunction "GND_5") (pintype "power_in"))
      (node (ref "MICRO-USB-B") (pin "6") (pinfunction "SHIELD5_6") (pintype "power_in"))
      (node (ref "MICRO-USB-B") (pin "7") (pinfunction "SHIELD6_7") (pintype "power_in"))
      (node (ref "MICRO-USB-B") (pin "SH1") (pinfunction "SHIELD1_SH1") (pintype "power_in"))
      (node (ref "MICRO-USB-B") (pin "SH2") (pinfunction "SHIELD2_SH2") (pintype "power_in"))
      (node (ref "MICRO-USB-B") (pin "SH3") (pinfunction "SHIELD3_SH3") (pintype "power_in"))
      (node (ref "MICRO-USB-B") (pin "SH4") (pinfunction "SHIELD4_SH4") (pintype "power_in"))
      (node (ref "PWR") (pin "C") (pinfunction "C_C") (pintype "passive"))
      (node (ref "R12") (pin "2") (pinfunction "2_2") (pintype "passive"))
      (node (ref "R14") (pin "1") (pinfunction "1_1") (pintype "passive"))
      (node (ref "R17") (pin "1") (pinfunction "1_1") (pintype "passive"))
      (node (ref "R6") (pin "2") (pinfunction "2_2") (pintype "passive"))
      (node (ref "RX") (pin "C") (pinfunction "C_C") (pintype "passive"))
      (node (ref "SD") (pin "6") (pinfunction "GND_6") (pintype "power_in"))
      (node (ref "SD") (pin "MT1") (pinfunction "GND_MT1") (pintype "power_in"))
      (node (ref "SD") (pin "MT2") (pinfunction "GND_MT2") (pintype "power_in"))
      (node (ref "SW1") (pin "3") (pinfunction "3_3") (pintype "passive"))
      (node (ref "SW1") (pin "4") (pinfunction "4_4") (pintype "passive"))
      (node (ref "SW2") (pin "3") (pinfunction "3_3") (pintype "passive"))
      (node (ref "SW2") (pin "4") (pinfunction "4_4") (pintype "passive"))
      (node (ref "TX") (pin "C") (pinfunction "C_C") (pintype "passive"))
      (node (ref "U1") (pin "18") (pinfunction "GND_18") (pintype "power_in"))
      (node (ref "U1") (pin "35") (pinfunction "GND_35") (pintype "power_in"))
      (node (ref "U1") (pin "42") (pinfunction "GND_42") (pintype "power_in"))
      (node (ref "U1") (pin "5") (pinfunction "GNDANA_5") (pintype "power_in"))
      (node (ref "U2") (pin "2") (pinfunction "VSS_2") (pintype "power_in"))
      (node (ref "U3") (pin "1") (pinfunction "GND_1") (pintype "power_in"))
      (node (ref "U4") (pin "3") (pinfunction "GND_3") (pintype "passive"))
      (node (ref "U4") (pin "6") (pinfunction "SDO_6") (pintype "output"))
      (node (ref "U5") (pin "1") (pinfunction "GND_1") (pintype "power_in"))
      (node (ref "U5") (pin "10") (pinfunction "GND_10") (pintype "power_in"))
      (node (ref "U5") (pin "8") (pinfunction "GND_8") (pintype "power_in"))
      (node (ref "U6") (pin "10") (pinfunction "GND_10") (pintype "bidirectional"))
      (node (ref "U6") (pin "12") (pinfunction "GND_12") (pintype "bidirectional"))
      (node (ref "U6") (pin "13") (pinfunction "GND_13") (pintype "bidirectional"))
      (node (ref "U6") (pin "24") (pinfunction "GND_24") (pintype "bidirectional"))
      (node (ref "U7") (pin "6") (pinfunction "GND_2_6") (pintype "passive"))
      (node (ref "U7") (pin "7") (pinfunction "GND_7") (pintype "passive"))
    )
    (net (code "47") (name "Net-(BLINK-PadA)") (class "Default")
      (node (ref "BLINK") (pin "A") (pinfunction "A_A") (pintype "passive"))
      (node (ref "R8") (pin "2") (pinfunction "2_2") (pintype "passive"))
    )
    (net (code "48") (name "Net-(CHGR-PadC)") (class "Default")
      (node (ref "CHGR") (pin "C") (pinfunction "C_C") (pintype "passive"))
      (node (ref "R5") (pin "2") (pinfunction "2_2") (pintype "passive"))
    )
    (net (code "49") (name "Net-(PWR-PadA)") (class "Default")
      (node (ref "PWR") (pin "A") (pinfunction "A_A") (pintype "passive"))
      (node (ref "R7") (pin "2") (pinfunction "2_2") (pintype "passive"))
    )
    (net (code "50") (name "Net-(R9-Pad2)") (class "Default")
      (node (ref "R9") (pin "2") (pinfunction "2_2") (pintype "passive"))
      (node (ref "TX") (pin "A") (pinfunction "A_A") (pintype "passive"))
    )
    (net (code "51") (name "Net-(R10-Pad2)") (class "Default")
      (node (ref "R10") (pin "2") (pinfunction "2_2") (pintype "passive"))
      (node (ref "RX") (pin "A") (pinfunction "A_A") (pintype "passive"))
    )
    (net (code "52") (name "Net-(U1-PA00)") (class "Default")
      (node (ref "C2") (pin "1") (pinfunction "1_1") (pintype "passive"))
      (node (ref "U1") (pin "1") (pinfunction "PA00_1") (pintype "output"))
      (node (ref "XTAL1") (pin "2") (pinfunction "2_2") (pintype "passive"))
    )
    (net (code "53") (name "Net-(U1-PA01)") (class "Default")
      (node (ref "C3") (pin "1") (pinfunction "1_1") (pintype "passive"))
      (node (ref "U1") (pin "2") (pinfunction "PA01_2") (pintype "output"))
      (node (ref "XTAL1") (pin "1") (pinfunction "1_1") (pintype "passive"))
    )
    (net (code "54") (name "Net-(U1-VDDCORE)") (class "Default")
      (node (ref "C1") (pin "1") (pinfunction "1_1") (pintype "passive"))
      (node (ref "U1") (pin "43") (pinfunction "VDDCORE_43") (pintype "power_in"))
    )
    (net (code "55") (name "Net-(U2-PROG)") (class "Default")
      (node (ref "R6") (pin "1") (pinfunction "1_1") (pintype "passive"))
      (node (ref "U2") (pin "5") (pinfunction "PROG_5") (pintype "input"))
    )
    (net (code "56") (name "Net-(U2-STAT)") (class "Default")
      (node (ref "R5") (pin "1") (pinfunction "1_1") (pintype "passive"))
      (node (ref "U2") (pin "1") (pinfunction "STAT_1") (pintype "output"))
    )
    (net (code "57") (name "Net-(U6-~{RST})") (class "Default")
      (node (ref "R15") (pin "1") (pinfunction "1_1") (pintype "passive"))
      (node (ref "U6") (pin "8") (pinfunction "~{RST}_8") (pintype "bidirectional"))
    )
    (net (code "58") (name "Net-(U7-SDO{slash}SA0)") (class "Default")
      (node (ref "R16") (pin "1") (pinfunction "1_1") (pintype "passive"))
      (node (ref "R17") (pin "2") (pinfunction "2_2") (pintype "passive"))
      (node (ref "U7") (pin "1") (pinfunction "SDO/SA0_1") (pintype "bidirectional"))
    )
    (net (code "59") (name "VBAT") (class "Default")
      (node (ref "C8") (pin "1") (pinfunction "1_1") (pintype "passive"))
      (node (ref "D2") (pin "A") (pinfunction "A_A") (pintype "passive"))
      (node (ref "J3") (pin "1") (pinfunction "1_1") (pintype "passive"))
      (node (ref "U2") (pin "3") (pinfunction "VBAT_3") (pintype "power_in"))
    )
    (net (code "60") (name "VBUS") (class "Default")
      (node (ref "C5") (pin "1") (pinfunction "1_1") (pintype "passive"))
      (node (ref "CHGR") (pin "A") (pinfunction "A_A") (pintype "passive"))
      (node (ref "D2") (pin "C") (pinfunction "C_C") (pintype "passive"))
      (node (ref "JP4") (pin "1") (pinfunction "1_1") (pintype "passive"))
      (node (ref "MICRO-USB-B") (pin "1") (pinfunction "VCC_1") (pintype "power_in"))
      (node (ref "U2") (pin "4") (pinfunction "VDD_4") (pintype "power_in"))
      (node (ref "U3") (pin "3") (pinfunction "IN_3") (pintype "input"))
    )
    (net (code "61") (name "unconnected-(MICRO-USB-B-ID-Pad4)") (class "Default")
      (node (ref "MICRO-USB-B") (pin "4") (pinfunction "ID_4") (pintype "bidirectional"))
    )
    (net (code "62") (name "unconnected-(SD-CARD_DETECT1-PadCD2)") (class "Default")
      (node (ref "SD") (pin "CD2") (pinfunction "CARD_DETECT1_CD2") (pintype "passive"))
    )
    (net (code "63") (name "unconnected-(SD-DAT1-Pad8)") (class "Default")
      (node (ref "SD") (pin "8") (pinfunction "DAT1_8") (pintype "bidirectional"))
    )
    (net (code "64") (name "unconnected-(SD-DAT2-Pad1)") (class "Default")
      (node (ref "SD") (pin "1") (pinfunction "DAT2_1") (pintype "bidirectional"))
    )
    (net (code "65") (name "unconnected-(U1-PA13-Pad22)") (class "Default")
      (node (ref "U1") (pin "22") (pinfunction "PA13_22") (pintype "bidirectional"))
    )
    (net (code "66") (name "unconnected-(U1-PA28-Pad41)") (class "Default")
      (node (ref "U1") (pin "41") (pinfunction "PA28_41") (pintype "bidirectional"))
    )
    (net (code "67") (name "unconnected-(U6-EXT_INT-Pad4)") (class "Default")
      (node (ref "U6") (pin "4") (pinfunction "EXT_INT_4") (pintype "bidirectional"))
    )
    (net (code "68") (name "unconnected-(U6-LNA_EN-Pad14)") (class "Default")
      (node (ref "U6") (pin "14") (pinfunction "LNA_EN_14") (pintype "bidirectional"))
    )
    (net (code "69") (name "unconnected-(U6-RESERVED-Pad15)") (class "Default")
      (node (ref "U6") (pin "15") (pinfunction "RESERVED_15") (pintype "no_connect"))
    )
    (net (code "70") (name "unconnected-(U6-RESERVED-Pad16)") (class "Default")
      (node (ref "U6") (pin "16") (pinfunction "RESERVED_16") (pintype "no_connect"))
    )
    (net (code "71") (name "unconnected-(U6-RESERVED-Pad17)") (class "Default")
      (node (ref "U6") (pin "17") (pinfunction "RESERVED_17") (pintype "no_connect"))
    )
    (net (code "72") (name "unconnected-(U6-RX{slash}SPI_MOSI-Pad21)") (class "Default")
      (node (ref "U6") (pin "21") (pinfunction "RX/SPI_MOSI_21") (pintype "bidirectional"))
    )
    (net (code "73") (name "unconnected-(U6-TIMEPULSE-Pad3)") (class "Default")
      (node (ref "U6") (pin "3") (pinfunction "TIMEPULSE_3") (pintype "bidirectional"))
    )
    (net (code "74") (name "unconnected-(U6-TX{slash}SPI_MISO-Pad20)") (class "Default")
      (node (ref "U6") (pin "20") (pinfunction "TX/SPI_MISO_20") (pintype "bidirectional"))
    )
    (net (code "75") (name "unconnected-(U6-USB_D+-Pad6)") (class "Default")
      (node (ref "U6") (pin "6") (pinfunction "USB_D+_6") (pintype "bidirectional"))
    )
    (net (code "76") (name "unconnected-(U6-USB_D--Pad5)") (class "Default")
      (node (ref "U6") (pin "5") (pinfunction "USB_D-_5") (pintype "bidirectional"))
    )
    (net (code "77") (name "unconnected-(U6-VCC_RF-Pad9)") (class "Default")
      (node (ref "U6") (pin "9") (pinfunction "VCC_RF_9") (pintype "bidirectional"))
    )
    (net (code "78") (name "unconnected-(U6-~{SAFEBOOT}-Pad1)") (class "Default")
      (node (ref "U6") (pin "1") (pinfunction "~{SAFEBOOT}_1") (pintype "bidirectional"))
    )
    (net (code "79") (name "unconnected-(U7-INT1-Pad4)") (class "Default")
      (node (ref "U7") (pin "4") (pinfunction "INT1_4") (pintype "output"))
    )
    (net (code "80") (name "unconnected-(U7-INT2-Pad9)") (class "Default")
      (node (ref "U7") (pin "9") (pinfunction "INT2_9") (pintype "output"))
    )
    (net (code "81") (name "unconnected-(U7-NC-Pad11)") (class "Default")
      (node (ref "U7") (pin "11") (pinfunction "NC_11") (pintype "no_connect"))
    )
    (net (code "82") (name "unconnected-(U7-NC_2-Pad10)") (class "Default")
      (node (ref "U7") (pin "10") (pinfunction "NC_2_10") (pintype "no_connect"))
    )
    (net (code "83") (name "unconnected-(U7-SCX-Pad3)") (class "Default")
      (node (ref "U7") (pin "3") (pinfunction "SCX_3") (pintype "passive"))
    )
    (net (code "84") (name "unconnected-(U7-SDX-Pad2)") (class "Default")
      (node (ref "U7") (pin "2") (pinfunction "SDX_2") (pintype "passive"))
    )
  )
)
